# Base.net
KiCad netlist of a schematic drawn in EAGLE
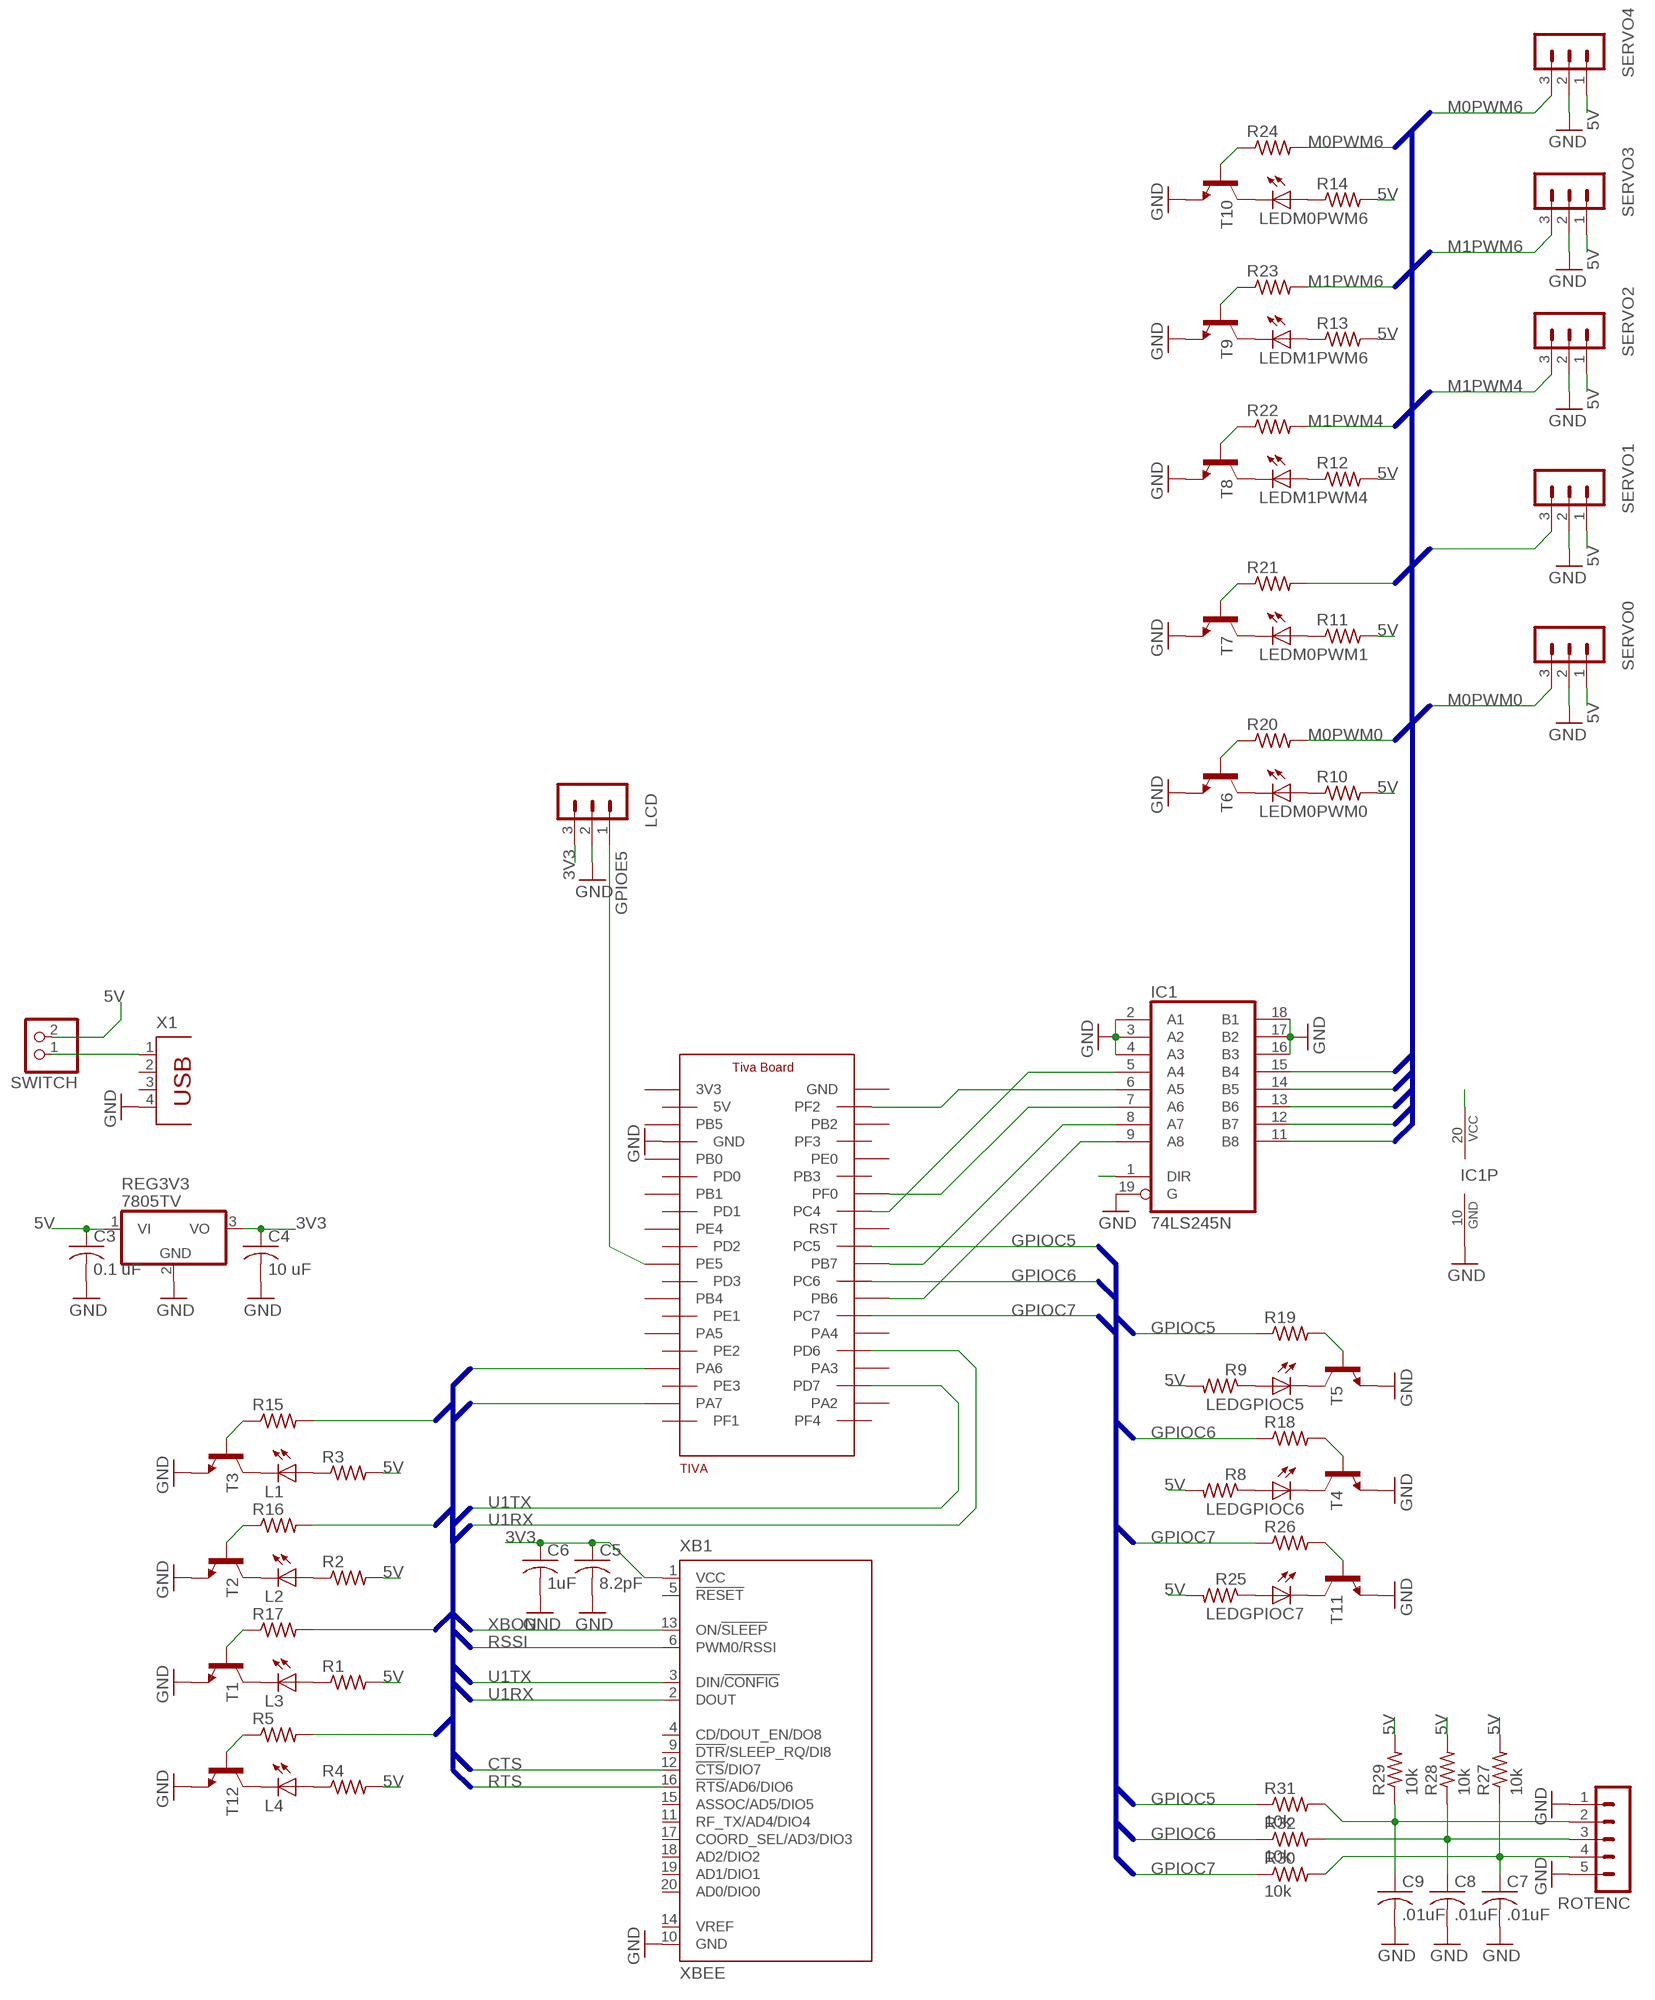
[diagram p0: schematic, sheet 1]

(export (version "E")
  (design (tool "Eeschema 10.0.6"))
  (components
    (comp (ref "C3")
      (value "0.1 uF")
      (footprint "eagle-import:C025-025X050")
      (libsource (lib "eagle-import") (part "C-US025-025X050"))
    )
    (comp (ref "C4")
      (value "10 uF")
      (footprint "eagle-import:C025-025X050")
      (libsource (lib "eagle-import") (part "C-US025-025X050"))
    )
    (comp (ref "C5")
      (value "8.2pF")
      (footprint "eagle-import:C025-025X050")
      (libsource (lib "eagle-import") (part "C-US025-025X050"))
    )
    (comp (ref "C6")
      (value "1uF")
      (footprint "eagle-import:C025-025X050")
      (libsource (lib "eagle-import") (part "C-US025-025X050"))
    )
    (comp (ref "C7")
      (value ".01uF")
      (footprint "eagle-import:C025-025X050")
      (libsource (lib "eagle-import") (part "C-US025-025X050"))
    )
    (comp (ref "C8")
      (value ".01uF")
      (footprint "eagle-import:C025-025X050")
      (libsource (lib "eagle-import") (part "C-US025-025X050"))
    )
    (comp (ref "C9")
      (value ".01uF")
      (footprint "eagle-import:C025-025X050")
      (libsource (lib "eagle-import") (part "C-US025-025X050"))
    )
    (comp (ref "IC1")
      (value "74LS245N")
      (footprint "eagle-import:DIL20")
      (libsource (lib "eagle-import") (part "74245NLS"))
    )
    (comp (ref "L1")
      (value "LED5MM")
      (footprint "eagle-import:LED5MM")
      (libsource (lib "eagle-import") (part "LED5MM"))
    )
    (comp (ref "L2")
      (value "LED5MM")
      (footprint "eagle-import:LED5MM")
      (libsource (lib "eagle-import") (part "LED5MM"))
    )
    (comp (ref "L3")
      (value "LED5MM")
      (footprint "eagle-import:LED5MM")
      (libsource (lib "eagle-import") (part "LED5MM"))
    )
    (comp (ref "L4")
      (value "LED5MM")
      (footprint "eagle-import:LED5MM")
      (libsource (lib "eagle-import") (part "LED5MM"))
    )
    (comp (ref "LCD")
      (value "MA03-1")
      (footprint "eagle-import:MA03-1")
      (libsource (lib "eagle-import") (part "MA03-1"))
    )
    (comp (ref "LEDGPIOC5")
      (value "LED5MM")
      (footprint "eagle-import:LED5MM")
      (libsource (lib "eagle-import") (part "LED5MM"))
    )
    (comp (ref "LEDGPIOC6")
      (value "LED5MM")
      (footprint "eagle-import:LED5MM")
      (libsource (lib "eagle-import") (part "LED5MM"))
    )
    (comp (ref "LEDGPIOC7")
      (value "LED5MM")
      (footprint "eagle-import:LED5MM")
      (libsource (lib "eagle-import") (part "LED5MM"))
    )
    (comp (ref "LEDM0PWM0")
      (value "LED5MM")
      (footprint "eagle-import:LED5MM")
      (libsource (lib "eagle-import") (part "LED5MM"))
    )
    (comp (ref "LEDM0PWM1")
      (value "LED5MM")
      (footprint "eagle-import:LED5MM")
      (libsource (lib "eagle-import") (part "LED5MM"))
    )
    (comp (ref "LEDM0PWM6")
      (value "LED5MM")
      (footprint "eagle-import:LED5MM")
      (libsource (lib "eagle-import") (part "LED5MM"))
    )
    (comp (ref "LEDM1PWM4")
      (value "LED5MM")
      (footprint "eagle-import:LED5MM")
      (libsource (lib "eagle-import") (part "LED5MM"))
    )
    (comp (ref "LEDM1PWM6")
      (value "LED5MM")
      (footprint "eagle-import:LED5MM")
      (libsource (lib "eagle-import") (part "LED5MM"))
    )
    (comp (ref "R1")
      (value "R-US_0207/7")
      (footprint "eagle-import:0207_7")
      (libsource (lib "eagle-import") (part "R-US_0207/7"))
    )
    (comp (ref "R2")
      (value "R-US_0207/7")
      (footprint "eagle-import:0207_7")
      (libsource (lib "eagle-import") (part "R-US_0207/7"))
    )
    (comp (ref "R3")
      (value "R-US_0207/7")
      (footprint "eagle-import:0207_7")
      (libsource (lib "eagle-import") (part "R-US_0207/7"))
    )
    (comp (ref "R4")
      (value "R-US_0207/7")
      (footprint "eagle-import:0207_7")
      (libsource (lib "eagle-import") (part "R-US_0207/7"))
    )
    (comp (ref "R5")
      (value "R-US_0207/7")
      (footprint "eagle-import:0207_7")
      (libsource (lib "eagle-import") (part "R-US_0207/7"))
    )
    (comp (ref "R8")
      (value "R-US_0207/7")
      (footprint "eagle-import:0207_7")
      (libsource (lib "eagle-import") (part "R-US_0207/7"))
    )
    (comp (ref "R9")
      (value "R-US_0207/7")
      (footprint "eagle-import:0207_7")
      (libsource (lib "eagle-import") (part "R-US_0207/7"))
    )
    (comp (ref "R10")
      (value "R-US_0207/7")
      (footprint "eagle-import:0207_7")
      (libsource (lib "eagle-import") (part "R-US_0207/7"))
    )
    (comp (ref "R11")
      (value "R-US_0207/7")
      (footprint "eagle-import:0207_7")
      (libsource (lib "eagle-import") (part "R-US_0207/7"))
    )
    (comp (ref "R12")
      (value "R-US_0207/7")
      (footprint "eagle-import:0207_7")
      (libsource (lib "eagle-import") (part "R-US_0207/7"))
    )
    (comp (ref "R13")
      (value "R-US_0207/7")
      (footprint "eagle-import:0207_7")
      (libsource (lib "eagle-import") (part "R-US_0207/7"))
    )
    (comp (ref "R14")
      (value "R-US_0207/7")
      (footprint "eagle-import:0207_7")
      (libsource (lib "eagle-import") (part "R-US_0207/7"))
    )
    (comp (ref "R15")
      (value "R-US_0207/7")
      (footprint "eagle-import:0207_7")
      (libsource (lib "eagle-import") (part "R-US_0207/7"))
    )
    (comp (ref "R16")
      (value "R-US_0207/7")
      (footprint "eagle-import:0207_7")
      (libsource (lib "eagle-import") (part "R-US_0207/7"))
    )
    (comp (ref "R17")
      (value "R-US_0207/7")
      (footprint "eagle-import:0207_7")
      (libsource (lib "eagle-import") (part "R-US_0207/7"))
    )
    (comp (ref "R18")
      (value "R-US_0207/7")
      (footprint "eagle-import:0207_7")
      (libsource (lib "eagle-import") (part "R-US_0207/7"))
    )
    (comp (ref "R19")
      (value "R-US_0207/7")
      (footprint "eagle-import:0207_7")
      (libsource (lib "eagle-import") (part "R-US_0207/7"))
    )
    (comp (ref "R20")
      (value "R-US_0207/7")
      (footprint "eagle-import:0207_7")
      (libsource (lib "eagle-import") (part "R-US_0207/7"))
    )
    (comp (ref "R21")
      (value "R-US_0207/7")
      (footprint "eagle-import:0207_7")
      (libsource (lib "eagle-import") (part "R-US_0207/7"))
    )
    (comp (ref "R22")
      (value "R-US_0207/7")
      (footprint "eagle-import:0207_7")
      (libsource (lib "eagle-import") (part "R-US_0207/7"))
    )
    (comp (ref "R23")
      (value "R-US_0207/7")
      (footprint "eagle-import:0207_7")
      (libsource (lib "eagle-import") (part "R-US_0207/7"))
    )
    (comp (ref "R24")
      (value "R-US_0207/7")
      (footprint "eagle-import:0207_7")
      (libsource (lib "eagle-import") (part "R-US_0207/7"))
    )
    (comp (ref "R25")
      (value "R-US_0207/7")
      (footprint "eagle-import:0207_7")
      (libsource (lib "eagle-import") (part "R-US_0207/7"))
    )
    (comp (ref "R26")
      (value "R-US_0207/7")
      (footprint "eagle-import:0207_7")
      (libsource (lib "eagle-import") (part "R-US_0207/7"))
    )
    (comp (ref "R27")
      (value "10k")
      (footprint "eagle-import:0207_7")
      (libsource (lib "eagle-import") (part "R-US_0207/7"))
    )
    (comp (ref "R28")
      (value "10k")
      (footprint "eagle-import:0207_7")
      (libsource (lib "eagle-import") (part "R-US_0207/7"))
    )
    (comp (ref "R29")
      (value "10k")
      (footprint "eagle-import:0207_7")
      (libsource (lib "eagle-import") (part "R-US_0207/7"))
    )
    (comp (ref "R30")
      (value "10k")
      (footprint "eagle-import:0207_7")
      (libsource (lib "eagle-import") (part "R-US_0207/7"))
    )
    (comp (ref "R31")
      (value "10k")
      (footprint "eagle-import:0207_7")
      (libsource (lib "eagle-import") (part "R-US_0207/7"))
    )
    (comp (ref "R32")
      (value "10k")
      (footprint "eagle-import:0207_7")
      (libsource (lib "eagle-import") (part "R-US_0207/7"))
    )
    (comp (ref "REG3V3")
      (value "7805TV")
      (footprint "eagle-import:TO220V")
      (libsource (lib "eagle-import") (part "78TV05"))
    )
    (comp (ref "ROTENC")
      (value "MA05-1")
      (footprint "eagle-import:MA05-1")
      (libsource (lib "eagle-import") (part "MA05-1"))
    )
    (comp (ref "SERVO0")
      (value "MA03-1")
      (footprint "eagle-import:MA03-1")
      (libsource (lib "eagle-import") (part "MA03-1"))
    )
    (comp (ref "SERVO1")
      (value "MA03-1")
      (footprint "eagle-import:MA03-1")
      (libsource (lib "eagle-import") (part "MA03-1"))
    )
    (comp (ref "SERVO2")
      (value "MA03-1")
      (footprint "eagle-import:MA03-1")
      (libsource (lib "eagle-import") (part "MA03-1"))
    )
    (comp (ref "SERVO3")
      (value "MA03-1")
      (footprint "eagle-import:MA03-1")
      (libsource (lib "eagle-import") (part "MA03-1"))
    )
    (comp (ref "SERVO4")
      (value "MA03-1")
      (footprint "eagle-import:MA03-1")
      (libsource (lib "eagle-import") (part "MA03-1"))
    )
    (comp (ref "SWITCH")
      (value "PINHD-1X2")
      (footprint "eagle-import:1X02")
      (libsource (lib "eagle-import") (part "PINHD-1X2"))
    )
    (comp (ref "T1")
      (value "2N3904")
      (footprint "eagle-import:TO92")
      (libsource (lib "eagle-import") (part "2N3904"))
    )
    (comp (ref "T2")
      (value "2N3904")
      (footprint "eagle-import:TO92")
      (libsource (lib "eagle-import") (part "2N3904"))
    )
    (comp (ref "T3")
      (value "2N3904")
      (footprint "eagle-import:TO92")
      (libsource (lib "eagle-import") (part "2N3904"))
    )
    (comp (ref "T4")
      (value "2N3904")
      (footprint "eagle-import:TO92")
      (libsource (lib "eagle-import") (part "2N3904"))
    )
    (comp (ref "T5")
      (value "2N3904")
      (footprint "eagle-import:TO92")
      (libsource (lib "eagle-import") (part "2N3904"))
    )
    (comp (ref "T6")
      (value "2N3904")
      (footprint "eagle-import:TO92")
      (libsource (lib "eagle-import") (part "2N3904"))
    )
    (comp (ref "T7")
      (value "2N3904")
      (footprint "eagle-import:TO92")
      (libsource (lib "eagle-import") (part "2N3904"))
    )
    (comp (ref "T8")
      (value "2N3904")
      (footprint "eagle-import:TO92")
      (libsource (lib "eagle-import") (part "2N3904"))
    )
    (comp (ref "T9")
      (value "2N3904")
      (footprint "eagle-import:TO92")
      (libsource (lib "eagle-import") (part "2N3904"))
    )
    (comp (ref "T10")
      (value "2N3904")
      (footprint "eagle-import:TO92")
      (libsource (lib "eagle-import") (part "2N3904"))
    )
    (comp (ref "T11")
      (value "2N3904")
      (footprint "eagle-import:TO92")
      (libsource (lib "eagle-import") (part "2N3904"))
    )
    (comp (ref "T12")
      (value "2N3904")
      (footprint "eagle-import:TO92")
      (libsource (lib "eagle-import") (part "2N3904"))
    )
    (comp (ref "TIVA")
      (value "TIVA-BOARD")
      (footprint "eagle-import:TIVA-BOARD")
      (libsource (lib "eagle-import") (part "TIVA-BOARD"))
    )
    (comp (ref "X1")
      (value "PN87520")
      (footprint "eagle-import:PN87520")
      (libsource (lib "eagle-import") (part "PN87520"))
    )
    (comp (ref "XB1")
      (value "XBEE")
      (footprint "eagle-import:XBEE")
      (fields (field (name "MPN") "XBP24-Z7UIT-004"))
      (libsource (lib "eagle-import") (part "XBEE"))
    )
  )
  (nets
    (net (code "1") (name "/3V3") (class "Default")
      (node (ref "C4") (pin "1") (pinfunction "1_1") (pintype "passive"))
      (node (ref "C5") (pin "1") (pinfunction "1_1") (pintype "passive"))
      (node (ref "C6") (pin "1") (pinfunction "1_1") (pintype "passive"))
      (node (ref "LCD") (pin "3") (pinfunction "3_3") (pintype "passive"))
      (node (ref "REG3V3") (pin "3") (pinfunction "VO_3") (pintype "passive"))
      (node (ref "XB1") (pin "1") (pinfunction "VCC_1") (pintype "power_in"))
    )
    (net (code "2") (name "/5V") (class "Default")
      (node (ref "C3") (pin "1") (pinfunction "1_1") (pintype "passive"))
      (node (ref "IC1") (pin "1") (pinfunction "DIR_1") (pintype "input"))
      (node (ref "IC1") (pin "20") (pinfunction "VCC_20") (pintype "power_in"))
      (node (ref "R1") (pin "2") (pinfunction "2_2") (pintype "passive"))
      (node (ref "R10") (pin "2") (pinfunction "2_2") (pintype "passive"))
      (node (ref "R11") (pin "2") (pinfunction "2_2") (pintype "passive"))
      (node (ref "R12") (pin "2") (pinfunction "2_2") (pintype "passive"))
      (node (ref "R13") (pin "2") (pinfunction "2_2") (pintype "passive"))
      (node (ref "R14") (pin "2") (pinfunction "2_2") (pintype "passive"))
      (node (ref "R2") (pin "2") (pinfunction "2_2") (pintype "passive"))
      (node (ref "R25") (pin "2") (pinfunction "2_2") (pintype "passive"))
      (node (ref "R27") (pin "2") (pinfunction "2_2") (pintype "passive"))
      (node (ref "R28") (pin "2") (pinfunction "2_2") (pintype "passive"))
      (node (ref "R29") (pin "2") (pinfunction "2_2") (pintype "passive"))
      (node (ref "R3") (pin "2") (pinfunction "2_2") (pintype "passive"))
      (node (ref "R4") (pin "2") (pinfunction "2_2") (pintype "passive"))
      (node (ref "R8") (pin "2") (pinfunction "2_2") (pintype "passive"))
      (node (ref "R9") (pin "2") (pinfunction "2_2") (pintype "passive"))
      (node (ref "REG3V3") (pin "1") (pinfunction "VI_1") (pintype "input"))
      (node (ref "SERVO0") (pin "1") (pinfunction "1_1") (pintype "passive"))
      (node (ref "SERVO1") (pin "1") (pinfunction "1_1") (pintype "passive"))
      (node (ref "SERVO2") (pin "1") (pinfunction "1_1") (pintype "passive"))
      (node (ref "SERVO3") (pin "1") (pinfunction "1_1") (pintype "passive"))
      (node (ref "SERVO4") (pin "1") (pinfunction "1_1") (pintype "passive"))
      (node (ref "SWITCH") (pin "2") (pinfunction "2_2") (pintype "passive"))
    )
    (net (code "3") (name "/CTS") (class "Default")
      (node (ref "TIVA") (pin "PA6") (pinfunction "PA6_PA6") (pintype "bidirectional"))
      (node (ref "XB1") (pin "12") (pinfunction "~{CTS}/DIO7_12") (pintype "bidirectional"))
    )
    (net (code "4") (name "/GPIOC5") (class "Default")
      (node (ref "R19") (pin "1") (pinfunction "1_1") (pintype "passive"))
      (node (ref "R31") (pin "1") (pinfunction "1_1") (pintype "passive"))
      (node (ref "TIVA") (pin "PC5") (pinfunction "PC5_PC5") (pintype "bidirectional"))
    )
    (net (code "5") (name "/GPIOC6") (class "Default")
      (node (ref "R18") (pin "1") (pinfunction "1_1") (pintype "passive"))
      (node (ref "R32") (pin "1") (pinfunction "1_1") (pintype "passive"))
      (node (ref "TIVA") (pin "PC6") (pinfunction "PC6_PC6") (pintype "bidirectional"))
    )
    (net (code "6") (name "/GPIOC7") (class "Default")
      (node (ref "R26") (pin "1") (pinfunction "1_1") (pintype "passive"))
      (node (ref "R30") (pin "1") (pinfunction "1_1") (pintype "passive"))
      (node (ref "TIVA") (pin "PC7") (pinfunction "PC7_PC7") (pintype "bidirectional"))
    )
    (net (code "7") (name "/GPIOE5") (class "Default")
      (node (ref "LCD") (pin "1") (pinfunction "1_1") (pintype "passive"))
      (node (ref "TIVA") (pin "PE5") (pinfunction "PE5_PE5") (pintype "bidirectional"))
    )
    (net (code "8") (name "/M0PWM0") (class "Default")
      (node (ref "IC1") (pin "11") (pinfunction "B8_11") (pintype "bidirectional"))
      (node (ref "R20") (pin "2") (pinfunction "2_2") (pintype "passive"))
      (node (ref "SERVO0") (pin "3") (pinfunction "3_3") (pintype "passive"))
    )
    (net (code "9") (name "/M0PWM1") (class "Default")
      (node (ref "IC1") (pin "12") (pinfunction "B7_12") (pintype "bidirectional"))
      (node (ref "R21") (pin "2") (pinfunction "2_2") (pintype "passive"))
      (node (ref "SERVO1") (pin "3") (pinfunction "3_3") (pintype "passive"))
    )
    (net (code "10") (name "/M0PWM6") (class "Default")
      (node (ref "IC1") (pin "15") (pinfunction "B4_15") (pintype "bidirectional"))
      (node (ref "R24") (pin "2") (pinfunction "2_2") (pintype "passive"))
      (node (ref "SERVO4") (pin "3") (pinfunction "3_3") (pintype "passive"))
    )
    (net (code "11") (name "/M1PWM4") (class "Default")
      (node (ref "IC1") (pin "13") (pinfunction "B6_13") (pintype "bidirectional"))
      (node (ref "R22") (pin "2") (pinfunction "2_2") (pintype "passive"))
      (node (ref "SERVO2") (pin "3") (pinfunction "3_3") (pintype "passive"))
    )
    (net (code "12") (name "/M1PWM6") (class "Default")
      (node (ref "IC1") (pin "14") (pinfunction "B5_14") (pintype "bidirectional"))
      (node (ref "R23") (pin "2") (pinfunction "2_2") (pintype "passive"))
      (node (ref "SERVO3") (pin "3") (pinfunction "3_3") (pintype "passive"))
    )
    (net (code "13") (name "/RSSI") (class "Default")
      (node (ref "R5") (pin "2") (pinfunction "2_2") (pintype "passive"))
      (node (ref "XB1") (pin "6") (pinfunction "PWM0/RSSI_6") (pintype "output"))
    )
    (net (code "14") (name "/RTS") (class "Default")
      (node (ref "TIVA") (pin "PA7") (pinfunction "PA7_PA7") (pintype "bidirectional"))
      (node (ref "XB1") (pin "16") (pinfunction "~{RTS}/AD6/DIO6_16") (pintype "bidirectional"))
    )
    (net (code "15") (name "/U1RX") (class "Default")
      (node (ref "R16") (pin "2") (pinfunction "2_2") (pintype "passive"))
      (node (ref "TIVA") (pin "PD6") (pinfunction "PD6_PD6") (pintype "bidirectional"))
      (node (ref "XB1") (pin "2") (pinfunction "DOUT_2") (pintype "output"))
    )
    (net (code "16") (name "/U1TX") (class "Default")
      (node (ref "R17") (pin "2") (pinfunction "2_2") (pintype "passive"))
      (node (ref "TIVA") (pin "PD7") (pinfunction "PD7_PD7") (pintype "bidirectional"))
      (node (ref "XB1") (pin "3") (pinfunction "DIN/~{CONFIG}_3") (pintype "input"))
    )
    (net (code "17") (name "/XBON") (class "Default")
      (node (ref "R15") (pin "2") (pinfunction "2_2") (pintype "passive"))
      (node (ref "XB1") (pin "13") (pinfunction "ON/~{SLEEP}_13") (pintype "output"))
    )
    (net (code "18") (name "GND") (class "Default")
      (node (ref "C3") (pin "2") (pinfunction "2_2") (pintype "passive"))
      (node (ref "C4") (pin "2") (pinfunction "2_2") (pintype "passive"))
      (node (ref "C5") (pin "2") (pinfunction "2_2") (pintype "passive"))
      (node (ref "C6") (pin "2") (pinfunction "2_2") (pintype "passive"))
      (node (ref "C7") (pin "2") (pinfunction "2_2") (pintype "passive"))
      (node (ref "C8") (pin "2") (pinfunction "2_2") (pintype "passive"))
      (node (ref "C9") (pin "2") (pinfunction "2_2") (pintype "passive"))
      (node (ref "IC1") (pin "10") (pinfunction "GND_10") (pintype "power_in"))
      (node (ref "IC1") (pin "16") (pinfunction "B3_16") (pintype "bidirectional"))
      (node (ref "IC1") (pin "17") (pinfunction "B2_17") (pintype "bidirectional"))
      (node (ref "IC1") (pin "18") (pinfunction "B1_18") (pintype "bidirectional"))
      (node (ref "IC1") (pin "19") (pinfunction "G_19") (pintype "input"))
      (node (ref "IC1") (pin "2") (pinfunction "A1_2") (pintype "bidirectional"))
      (node (ref "IC1") (pin "3") (pinfunction "A2_3") (pintype "bidirectional"))
      (node (ref "IC1") (pin "4") (pinfunction "A3_4") (pintype "bidirectional"))
      (node (ref "LCD") (pin "2") (pinfunction "2_2") (pintype "passive"))
      (node (ref "REG3V3") (pin "2") (pinfunction "GND_2") (pintype "passive"))
      (node (ref "ROTENC") (pin "1") (pinfunction "1_1") (pintype "passive"))
      (node (ref "ROTENC") (pin "5") (pinfunction "5_5") (pintype "passive"))
      (node (ref "SERVO0") (pin "2") (pinfunction "2_2") (pintype "passive"))
      (node (ref "SERVO1") (pin "2") (pinfunction "2_2") (pintype "passive"))
      (node (ref "SERVO2") (pin "2") (pinfunction "2_2") (pintype "passive"))
      (node (ref "SERVO3") (pin "2") (pinfunction "2_2") (pintype "passive"))
      (node (ref "SERVO4") (pin "2") (pinfunction "2_2") (pintype "passive"))
      (node (ref "T1") (pin "3") (pinfunction "E_3") (pintype "passive"))
      (node (ref "T10") (pin "3") (pinfunction "E_3") (pintype "passive"))
      (node (ref "T11") (pin "3") (pinfunction "E_3") (pintype "passive"))
      (node (ref "T12") (pin "3") (pinfunction "E_3") (pintype "passive"))
      (node (ref "T2") (pin "3") (pinfunction "E_3") (pintype "passive"))
      (node (ref "T3") (pin "3") (pinfunction "E_3") (pintype "passive"))
      (node (ref "T4") (pin "3") (pinfunction "E_3") (pintype "passive"))
      (node (ref "T5") (pin "3") (pinfunction "E_3") (pintype "passive"))
      (node (ref "T6") (pin "3") (pinfunction "E_3") (pintype "passive"))
      (node (ref "T7") (pin "3") (pinfunction "E_3") (pintype "passive"))
      (node (ref "T8") (pin "3") (pinfunction "E_3") (pintype "passive"))
      (node (ref "T9") (pin "3") (pinfunction "E_3") (pintype "passive"))
      (node (ref "TIVA") (pin "GND@1") (pinfunction "GND_GND@1") (pintype "bidirectional"))
      (node (ref "X1") (pin "4") (pinfunction "4_4") (pintype "passive"))
      (node (ref "XB1") (pin "10") (pinfunction "GND_10") (pintype "power_in"))
    )
    (net (code "19") (name "Net-(C7-Pad1)") (class "Default")
      (node (ref "C7") (pin "1") (pinfunction "1_1") (pintype "passive"))
      (node (ref "R27") (pin "1") (pinfunction "1_1") (pintype "passive"))
      (node (ref "R30") (pin "2") (pinfunction "2_2") (pintype "passive"))
      (node (ref "ROTENC") (pin "4") (pinfunction "4_4") (pintype "passive"))
    )
    (net (code "20") (name "Net-(C8-Pad1)") (class "Default")
      (node (ref "C8") (pin "1") (pinfunction "1_1") (pintype "passive"))
      (node (ref "R28") (pin "1") (pinfunction "1_1") (pintype "passive"))
      (node (ref "R32") (pin "2") (pinfunction "2_2") (pintype "passive"))
      (node (ref "ROTENC") (pin "3") (pinfunction "3_3") (pintype "passive"))
    )
    (net (code "21") (name "Net-(C9-Pad1)") (class "Default")
      (node (ref "C9") (pin "1") (pinfunction "1_1") (pintype "passive"))
      (node (ref "R29") (pin "1") (pinfunction "1_1") (pintype "passive"))
      (node (ref "R31") (pin "2") (pinfunction "2_2") (pintype "passive"))
      (node (ref "ROTENC") (pin "2") (pinfunction "2_2") (pintype "passive"))
    )
    (net (code "22") (name "Net-(IC1A-A4)") (class "Default")
      (node (ref "IC1") (pin "5") (pinfunction "A4_5") (pintype "bidirectional"))
      (node (ref "TIVA") (pin "PC4") (pinfunction "PC4_PC4") (pintype "bidirectional"))
    )
    (net (code "23") (name "Net-(IC1A-A5)") (class "Default")
      (node (ref "IC1") (pin "6") (pinfunction "A5_6") (pintype "bidirectional"))
      (node (ref "TIVA") (pin "PF2") (pinfunction "PF2_PF2") (pintype "bidirectional"))
    )
    (net (code "24") (name "Net-(IC1A-A6)") (class "Default")
      (node (ref "IC1") (pin "7") (pinfunction "A6_7") (pintype "bidirectional"))
      (node (ref "TIVA") (pin "PF0") (pinfunction "PF0_PF0") (pintype "bidirectional"))
    )
    (net (code "25") (name "Net-(IC1A-A7)") (class "Default")
      (node (ref "IC1") (pin "8") (pinfunction "A7_8") (pintype "bidirectional"))
      (node (ref "TIVA") (pin "PB7") (pinfunction "PB7_PB7") (pintype "bidirectional"))
    )
    (net (code "26") (name "Net-(IC1A-A8)") (class "Default")
      (node (ref "IC1") (pin "9") (pinfunction "A8_9") (pintype "bidirectional"))
      (node (ref "TIVA") (pin "PB6") (pinfunction "PB6_PB6") (pintype "bidirectional"))
    )
    (net (code "27") (name "Net-(L1-C)") (class "Default")
      (node (ref "L1") (pin "K") (pinfunction "C_K") (pintype "passive"))
      (node (ref "T3") (pin "1") (pinfunction "C_1") (pintype "passive"))
    )
    (net (code "28") (name "Net-(L1-PadA)") (class "Default")
      (node (ref "L1") (pin "A") (pinfunction "A_A") (pintype "passive"))
      (node (ref "R3") (pin "1") (pinfunction "1_1") (pintype "passive"))
    )
    (net (code "29") (name "Net-(L2-C)") (class "Default")
      (node (ref "L2") (pin "K") (pinfunction "C_K") (pintype "passive"))
      (node (ref "T2") (pin "1") (pinfunction "C_1") (pintype "passive"))
    )
    (net (code "30") (name "Net-(L2-PadA)") (class "Default")
      (node (ref "L2") (pin "A") (pinfunction "A_A") (pintype "passive"))
      (node (ref "R2") (pin "1") (pinfunction "1_1") (pintype "passive"))
    )
    (net (code "31") (name "Net-(L3-C)") (class "Default")
      (node (ref "L3") (pin "K") (pinfunction "C_K") (pintype "passive"))
      (node (ref "T1") (pin "1") (pinfunction "C_1") (pintype "passive"))
    )
    (net (code "32") (name "Net-(L3-PadA)") (class "Default")
      (node (ref "L3") (pin "A") (pinfunction "A_A") (pintype "passive"))
      (node (ref "R1") (pin "1") (pinfunction "1_1") (pintype "passive"))
    )
    (net (code "33") (name "Net-(L4-C)") (class "Default")
      (node (ref "L4") (pin "K") (pinfunction "C_K") (pintype "passive"))
      (node (ref "T12") (pin "1") (pinfunction "C_1") (pintype "passive"))
    )
    (net (code "34") (name "Net-(L4-PadA)") (class "Default")
      (node (ref "L4") (pin "A") (pinfunction "A_A") (pintype "passive"))
      (node (ref "R4") (pin "1") (pinfunction "1_1") (pintype "passive"))
    )
    (net (code "35") (name "Net-(LEDGPIOC5-C)") (class "Default")
      (node (ref "LEDGPIOC5") (pin "K") (pinfunction "C_K") (pintype "passive"))
      (node (ref "T5") (pin "1") (pinfunction "C_1") (pintype "passive"))
    )
    (net (code "36") (name "Net-(LEDGPIOC5-PadA)") (class "Default")
      (node (ref "LEDGPIOC5") (pin "A") (pinfunction "A_A") (pintype "passive"))
      (node (ref "R9") (pin "1") (pinfunction "1_1") (pintype "passive"))
    )
    (net (code "37") (name "Net-(LEDGPIOC6-C)") (class "Default")
      (node (ref "LEDGPIOC6") (pin "K") (pinfunction "C_K") (pintype "passive"))
      (node (ref "T4") (pin "1") (pinfunction "C_1") (pintype "passive"))
    )
    (net (code "38") (name "Net-(LEDGPIOC6-PadA)") (class "Default")
      (node (ref "LEDGPIOC6") (pin "A") (pinfunction "A_A") (pintype "passive"))
      (node (ref "R8") (pin "1") (pinfunction "1_1") (pintype "passive"))
    )
    (net (code "39") (name "Net-(LEDGPIOC7-C)") (class "Default")
      (node (ref "LEDGPIOC7") (pin "K") (pinfunction "C_K") (pintype "passive"))
      (node (ref "T11") (pin "1") (pinfunction "C_1") (pintype "passive"))
    )
    (net (code "40") (name "Net-(LEDGPIOC7-PadA)") (class "Default")
      (node (ref "LEDGPIOC7") (pin "A") (pinfunction "A_A") (pintype "passive"))
      (node (ref "R25") (pin "1") (pinfunction "1_1") (pintype "passive"))
    )
    (net (code "41") (name "Net-(LEDM0PWM0-C)") (class "Default")
      (node (ref "LEDM0PWM0") (pin "K") (pinfunction "C_K") (pintype "passive"))
      (node (ref "T6") (pin "1") (pinfunction "C_1") (pintype "passive"))
    )
    (net (code "42") (name "Net-(LEDM0PWM0-PadA)") (class "Default")
      (node (ref "LEDM0PWM0") (pin "A") (pinfunction "A_A") (pintype "passive"))
      (node (ref "R10") (pin "1") (pinfunction "1_1") (pintype "passive"))
    )
    (net (code "43") (name "Net-(LEDM0PWM1-C)") (class "Default")
      (node (ref "LEDM0PWM1") (pin "K") (pinfunction "C_K") (pintype "passive"))
      (node (ref "T7") (pin "1") (pinfunction "C_1") (pintype "passive"))
    )
    (net (code "44") (name "Net-(LEDM0PWM1-PadA)") (class "Default")
      (node (ref "LEDM0PWM1") (pin "A") (pinfunction "A_A") (pintype "passive"))
      (node (ref "R11") (pin "1") (pinfunction "1_1") (pintype "passive"))
    )
    (net (code "45") (name "Net-(LEDM0PWM6-C)") (class "Default")
      (node (ref "LEDM0PWM6") (pin "K") (pinfunction "C_K") (pintype "passive"))
      (node (ref "T10") (pin "1") (pinfunction "C_1") (pintype "passive"))
    )
    (net (code "46") (name "Net-(LEDM0PWM6-PadA)") (class "Default")
      (node (ref "LEDM0PWM6") (pin "A") (pinfunction "A_A") (pintype "passive"))
      (node (ref "R14") (pin "1") (pinfunction "1_1") (pintype "passive"))
    )
    (net (code "47") (name "Net-(LEDM1PWM4-C)") (class "Default")
      (node (ref "LEDM1PWM4") (pin "K") (pinfunction "C_K") (pintype "passive"))
      (node (ref "T8") (pin "1") (pinfunction "C_1") (pintype "passive"))
    )
    (net (code "48") (name "Net-(LEDM1PWM4-PadA)") (class "Default")
      (node (ref "LEDM1PWM4") (pin "A") (pinfunction "A_A") (pintype "passive"))
      (node (ref "R12") (pin "1") (pinfunction "1_1") (pintype "passive"))
    )
    (net (code "49") (name "Net-(LEDM1PWM6-C)") (class "Default")
      (node (ref "LEDM1PWM6") (pin "K") (pinfunction "C_K") (pintype "passive"))
      (node (ref "T9") (pin "1") (pinfunction "C_1") (pintype "passive"))
    )
    (net (code "50") (name "Net-(LEDM1PWM6-PadA)") (class "Default")
      (node (ref "LEDM1PWM6") (pin "A") (pinfunction "A_A") (pintype "passive"))
      (node (ref "R13") (pin "1") (pinfunction "1_1") (pintype "passive"))
    )
    (net (code "51") (name "Net-(SWITCH-Pad1)") (class "Default")
      (node (ref "SWITCH") (pin "1") (pinfunction "1_1") (pintype "passive"))
      (node (ref "X1") (pin "1") (pinfunction "1_1") (pintype "passive"))
    )
    (net (code "52") (name "Net-(T1-B)") (class "Default")
      (node (ref "R17") (pin "1") (pinfunction "1_1") (pintype "passive"))
      (node (ref "T1") (pin "2") (pinfunction "B_2") (pintype "passive"))
    )
    (net (code "53") (name "Net-(T2-B)") (class "Default")
      (node (ref "R16") (pin "1") (pinfunction "1_1") (pintype "passive"))
      (node (ref "T2") (pin "2") (pinfunction "B_2") (pintype "passive"))
    )
    (net (code "54") (name "Net-(T3-B)") (class "Default")
      (node (ref "R15") (pin "1") (pinfunction "1_1") (pintype "passive"))
      (node (ref "T3") (pin "2") (pinfunction "B_2") (pintype "passive"))
    )
    (net (code "55") (name "Net-(T4-B)") (class "Default")
      (node (ref "R18") (pin "2") (pinfunction "2_2") (pintype "passive"))
      (node (ref "T4") (pin "2") (pinfunction "B_2") (pintype "passive"))
    )
    (net (code "56") (name "Net-(T5-B)") (class "Default")
      (node (ref "R19") (pin "2") (pinfunction "2_2") (pintype "passive"))
      (node (ref "T5") (pin "2") (pinfunction "B_2") (pintype "passive"))
    )
    (net (code "57") (name "Net-(T6-B)") (class "Default")
      (node (ref "R20") (pin "1") (pinfunction "1_1") (pintype "passive"))
      (node (ref "T6") (pin "2") (pinfunction "B_2") (pintype "passive"))
    )
    (net (code "58") (name "Net-(T7-B)") (class "Default")
      (node (ref "R21") (pin "1") (pinfunction "1_1") (pintype "passive"))
      (node (ref "T7") (pin "2") (pinfunction "B_2") (pintype "passive"))
    )
    (net (code "59") (name "Net-(T8-B)") (class "Default")
      (node (ref "R22") (pin "1") (pinfunction "1_1") (pintype "passive"))
      (node (ref "T8") (pin "2") (pinfunction "B_2") (pintype "passive"))
    )
    (net (code "60") (name "Net-(T9-B)") (class "Default")
      (node (ref "R23") (pin "1") (pinfunction "1_1") (pintype "passive"))
      (node (ref "T9") (pin "2") (pinfunction "B_2") (pintype "passive"))
    )
    (net (code "61") (name "Net-(T10-B)") (class "Default")
      (node (ref "R24") (pin "1") (pinfunction "1_1") (pintype "passive"))
      (node (ref "T10") (pin "2") (pinfunction "B_2") (pintype "passive"))
    )
    (net (code "62") (name "Net-(T11-B)") (class "Default")
      (node (ref "R26") (pin "2") (pinfunction "2_2") (pintype "passive"))
      (node (ref "T11") (pin "2") (pinfunction "B_2") (pintype "passive"))
    )
    (net (code "63") (name "Net-(T12-B)") (class "Default")
      (node (ref "R5") (pin "1") (pinfunction "1_1") (pintype "passive"))
      (node (ref "T12") (pin "2") (pinfunction "B_2") (pintype "passive"))
    )
    (net (code "64") (name "unconnected-(TIVA-3V3-Pad3.3V)") (class "Default")
      (node (ref "TIVA") (pin "3.3V") (pinfunction "3V3_3.3V") (pintype "bidirectional"))
    )
    (net (code "65") (name "unconnected-(TIVA-GND-PadGND@2)") (class "Default")
      (node (ref "TIVA") (pin "GND@2") (pinfunction "GND_GND@2") (pintype "bidirectional"))
    )
    (net (code "66") (name "unconnected-(TIVA-Pad5V)") (class "Default")
      (node (ref "TIVA") (pin "5V") (pinfunction "5V_5V") (pintype "bidirectional"))
    )
    (net (code "67") (name "unconnected-(TIVA-PadPA2)") (class "Default")
      (node (ref "TIVA") (pin "PA2") (pinfunction "PA2_PA2") (pintype "bidirectional"))
    )
    (net (code "68") (name "unconnected-(TIVA-PadPA3)") (class "Default")
      (node (ref "TIVA") (pin "PA3") (pinfunction "PA3_PA3") (pintype "bidirectional"))
    )
    (net (code "69") (name "unconnected-(TIVA-PadPA4)") (class "Default")
      (node (ref "TIVA") (pin "PA4") (pinfunction "PA4_PA4") (pintype "bidirectional"))
    )
    (net (code "70") (name "unconnected-(TIVA-PadPA5)") (class "Default")
      (node (ref "TIVA") (pin "PA5") (pinfunction "PA5_PA5") (pintype "bidirectional"))
    )
    (net (code "71") (name "unconnected-(TIVA-PadPB0)") (class "Default")
      (node (ref "TIVA") (pin "PB0") (pinfunction "PB0_PB0") (pintype "bidirectional"))
    )
    (net (code "72") (name "unconnected-(TIVA-PadPB1)") (class "Default")
      (node (ref "TIVA") (pin "PB1") (pinfunction "PB1_PB1") (pintype "bidirectional"))
    )
    (net (code "73") (name "unconnected-(TIVA-PadPB2)") (class "Default")
      (node (ref "TIVA") (pin "PB2") (pinfunction "PB2_PB2") (pintype "bidirectional"))
    )
    (net (code "74") (name "unconnected-(TIVA-PadPB3)") (class "Default")
      (node (ref "TIVA") (pin "PB3") (pinfunction "PB3_PB3") (pintype "bidirectional"))
    )
    (net (code "75") (name "unconnected-(TIVA-PadPB4)") (class "Default")
      (node (ref "TIVA") (pin "PB4") (pinfunction "PB4_PB4") (pintype "bidirectional"))
    )
    (net (code "76") (name "unconnected-(TIVA-PadPB5)") (class "Default")
      (node (ref "TIVA") (pin "PB5") (pinfunction "PB5_PB5") (pintype "bidirectional"))
    )
    (net (code "77") (name "unconnected-(TIVA-PadPD0)") (class "Default")
      (node (ref "TIVA") (pin "PD0") (pinfunction "PD0_PD0") (pintype "bidirectional"))
    )
    (net (code "78") (name "unconnected-(TIVA-PadPD1)") (class "Default")
      (node (ref "TIVA") (pin "PD1") (pinfunction "PD1_PD1") (pintype "bidirectional"))
    )
    (net (code "79") (name "unconnected-(TIVA-PadPD2)") (class "Default")
      (node (ref "TIVA") (pin "PD2") (pinfunction "PD2_PD2") (pintype "bidirectional"))
    )
    (net (code "80") (name "unconnected-(TIVA-PadPD3)") (class "Default")
      (node (ref "TIVA") (pin "PD3") (pinfunction "PD3_PD3") (pintype "bidirectional"))
    )
    (net (code "81") (name "unconnected-(TIVA-PadPE0)") (class "Default")
      (node (ref "TIVA") (pin "PE0") (pinfunction "PE0_PE0") (pintype "bidirectional"))
    )
    (net (code "82") (name "unconnected-(TIVA-PadPE1)") (class "Default")
      (node (ref "TIVA") (pin "PE1") (pinfunction "PE1_PE1") (pintype "bidirectional"))
    )
    (net (code "83") (name "unconnected-(TIVA-PadPE2)") (class "Default")
      (node (ref "TIVA") (pin "PE2") (pinfunction "PE2_PE2") (pintype "bidirectional"))
    )
    (net (code "84") (name "unconnected-(TIVA-PadPE3)") (class "Default")
      (node (ref "TIVA") (pin "PE3") (pinfunction "PE3_PE3") (pintype "bidirectional"))
    )
    (net (code "85") (name "unconnected-(TIVA-PadPE4)") (class "Default")
      (node (ref "TIVA") (pin "PE4") (pinfunction "PE4_PE4") (pintype "bidirectional"))
    )
    (net (code "86") (name "unconnected-(TIVA-PadPF1)") (class "Default")
      (node (ref "TIVA") (pin "PF1") (pinfunction "PF1_PF1") (pintype "bidirectional"))
    )
    (net (code "87") (name "unconnected-(TIVA-PadPF3)") (class "Default")
      (node (ref "TIVA") (pin "PF3") (pinfunction "PF3_PF3") (pintype "bidirectional"))
    )
    (net (code "88") (name "unconnected-(TIVA-PadPF4)") (class "Default")
      (node (ref "TIVA") (pin "PF4") (pinfunction "PF4_PF4") (pintype "bidirectional"))
    )
    (net (code "89") (name "unconnected-(TIVA-PadRST)") (class "Default")
      (node (ref "TIVA") (pin "RST") (pinfunction "RST_RST") (pintype "bidirectional"))
    )
    (net (code "90") (name "unconnected-(X1-Pad2)") (class "Default")
      (node (ref "X1") (pin "2") (pinfunction "2_2") (pintype "passive"))
    )
    (net (code "91") (name "unconnected-(X1-Pad3)") (class "Default")
      (node (ref "X1") (pin "3") (pinfunction "3_3") (pintype "passive"))
    )
    (net (code "92") (name "unconnected-(XB1-AD0{slash}DIO0-Pad20)") (class "Default")
      (node (ref "XB1") (pin "20") (pinfunction "AD0/DIO0_20") (pintype "bidirectional"))
    )
    (net (code "93") (name "unconnected-(XB1-AD1{slash}DIO1-Pad19)") (class "Default")
      (node (ref "XB1") (pin "19") (pinfunction "AD1/DIO1_19") (pintype "bidirectional"))
    )
    (net (code "94") (name "unconnected-(XB1-AD2{slash}DIO2-Pad18)") (class "Default")
      (node (ref "XB1") (pin "18") (pinfunction "AD2/DIO2_18") (pintype "bidirectional"))
    )
    (net (code "95") (name "unconnected-(XB1-ASSOC{slash}AD5{slash}DIO5-Pad15)") (class "Default")
      (node (ref "XB1") (pin "15") (pinfunction "ASSOC/AD5/DIO5_15") (pintype "bidirectional"))
    )
    (net (code "96") (name "unconnected-(XB1-CD{slash}DOUT_EN{slash}DO8-Pad4)") (class "Default")
      (node (ref "XB1") (pin "4") (pinfunction "CD/DOUT_EN/DO8_4") (pintype "output"))
    )
    (net (code "97") (name "unconnected-(XB1-COORD_SEL{slash}AD3{slash}DIO3-Pad17)") (class "Default")
      (node (ref "XB1") (pin "17") (pinfunction "COORD_SEL/AD3/DIO3_17") (pintype "bidirectional"))
    )
    (net (code "98") (name "unconnected-(XB1-RF_TX{slash}AD4{slash}DIO4-Pad11)") (class "Default")
      (node (ref "XB1") (pin "11") (pinfunction "RF_TX/AD4/DIO4_11") (pintype "bidirectional"))
    )
    (net (code "99") (name "unconnected-(XB1-VREF-Pad14)") (class "Default")
      (node (ref "XB1") (pin "14") (pinfunction "VREF_14") (pintype "input"))
    )
    (net (code "100") (name "unconnected-(XB1-~{DTR}{slash}SLEEP_RQ{slash}DI8-Pad9)") (class "Default")
      (node (ref "XB1") (pin "9") (pinfunction "~{DTR}/SLEEP_RQ/DI8_9") (pintype "bidirectional"))
    )
    (net (code "101") (name "unconnected-(XB1-~{RESET}-Pad5)") (class "Default")
      (node (ref "XB1") (pin "5") (pinfunction "~{RESET}_5") (pintype "input"))
    )
  )
)
